# RGB_Panel_v-1.net
KiCad netlist of a schematic drawn in EAGLE
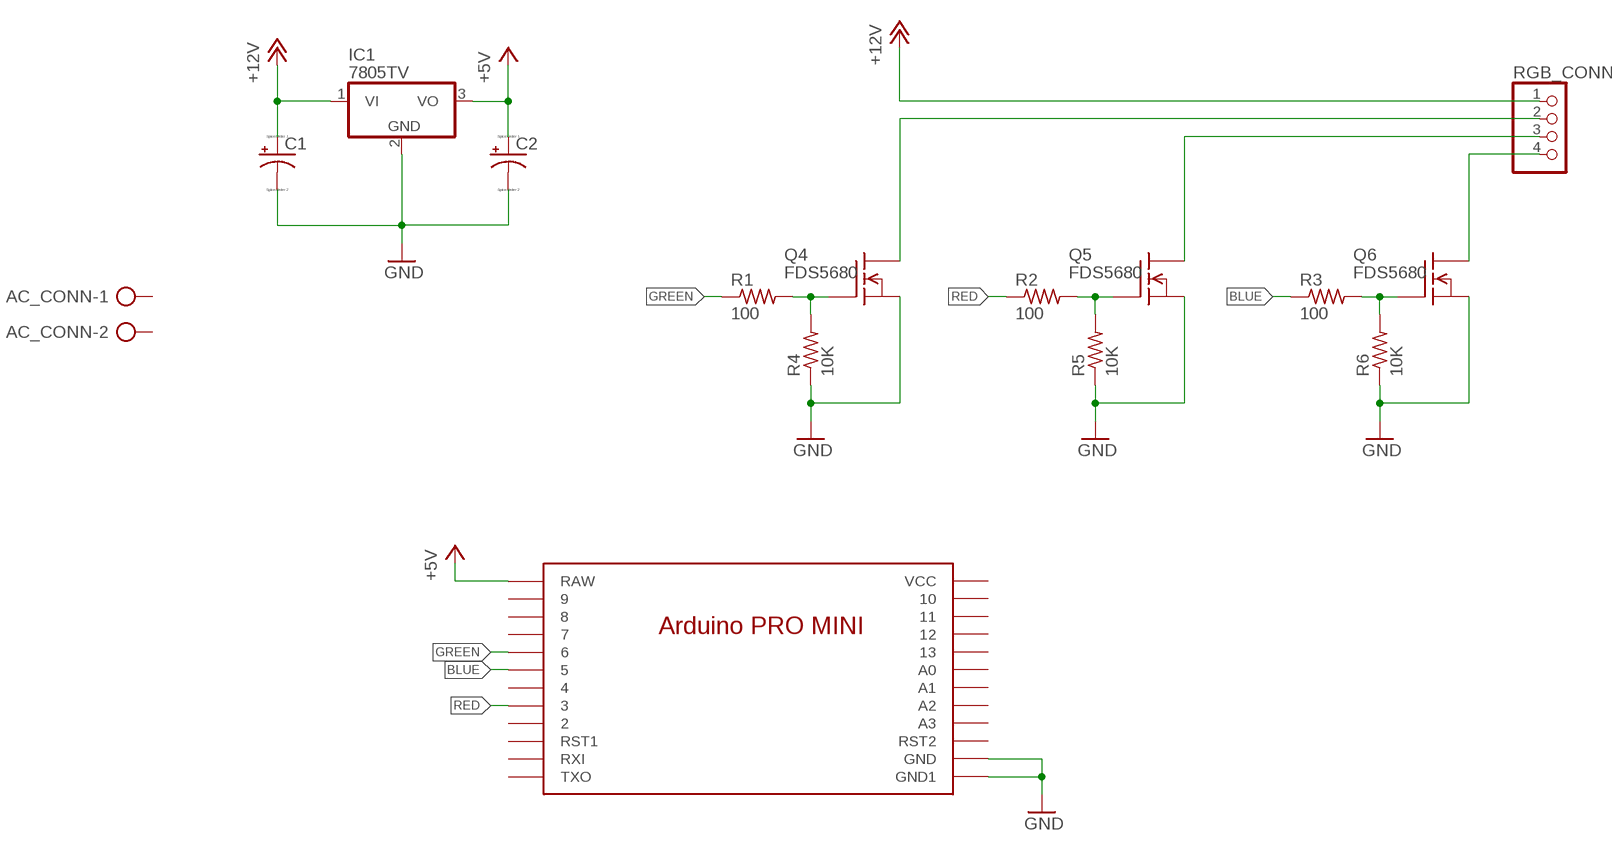
[diagram p0: schematic, sheet 1]

(export (version "E")
  (design (tool "Eeschema 10.0.6"))
  (components
    (comp (ref "AC_CONN")
      (value "AK300/2")
      (footprint "eagle-import:AK300_2")
      (libsource (lib "eagle-import") (part "AK300/2"))
    )
    (comp (ref "C1")
      (value "CPOL-USE2,5-6E")
      (footprint "eagle-import:E2,5-6E")
      (libsource (lib "eagle-import") (part "CPOL-USE2,5-6E"))
    )
    (comp (ref "C2")
      (value "CPOL-USE2,5-6E")
      (footprint "eagle-import:E2,5-6E")
      (libsource (lib "eagle-import") (part "CPOL-USE2,5-6E"))
    )
    (comp (ref "IC1")
      (value "7805TV")
      (footprint "eagle-import:TO220V")
      (libsource (lib "eagle-import") (part "78TV05"))
    )
    (comp (ref "Q4")
      (value "FDS5680")
      (footprint "eagle-import:SO-8")
      (libsource (lib "eagle-import") (part "FDS5680"))
    )
    (comp (ref "Q5")
      (value "FDS5680")
      (footprint "eagle-import:SO-8")
      (libsource (lib "eagle-import") (part "FDS5680"))
    )
    (comp (ref "Q6")
      (value "FDS5680")
      (footprint "eagle-import:SO-8")
      (libsource (lib "eagle-import") (part "FDS5680"))
    )
    (comp (ref "R1")
      (value "100")
      (footprint "eagle-import:0204_7")
      (libsource (lib "eagle-import") (part "R-US_0204/7"))
    )
    (comp (ref "R2")
      (value "100")
      (footprint "eagle-import:0204_7")
      (libsource (lib "eagle-import") (part "R-US_0204/7"))
    )
    (comp (ref "R3")
      (value "100")
      (footprint "eagle-import:0204_7")
      (libsource (lib "eagle-import") (part "R-US_0204/7"))
    )
    (comp (ref "R4")
      (value "10K")
      (footprint "eagle-import:0204_7")
      (libsource (lib "eagle-import") (part "R-US_0204/7"))
    )
    (comp (ref "R5")
      (value "10K")
      (footprint "eagle-import:0204_7")
      (libsource (lib "eagle-import") (part "R-US_0204/7"))
    )
    (comp (ref "R6")
      (value "10K")
      (footprint "eagle-import:0204_7")
      (libsource (lib "eagle-import") (part "R-US_0204/7"))
    )
    (comp (ref "RGB_CONN")
      (value "PINHD-1X4")
      (footprint "eagle-import:1X04")
      (libsource (lib "eagle-import") (part "PINHD-1X4"))
    )
    (comp (ref "U$1")
      (value "NANO")
      (footprint "eagle-import:NANO")
      (libsource (lib "eagle-import") (part "NANO"))
    )
  )
  (nets
    (net (code "1") (name "+5V") (class "Default")
      (node (ref "C2") (pin "+") (pinfunction "+_+") (pintype "passive"))
      (node (ref "IC1") (pin "3") (pinfunction "VO_3") (pintype "passive"))
      (node (ref "U$1") (pin "RAW") (pinfunction "RAW_RAW") (pintype "bidirectional"))
    )
    (net (code "2") (name "+12V") (class "Default")
      (node (ref "C1") (pin "+") (pinfunction "+_+") (pintype "passive"))
      (node (ref "IC1") (pin "1") (pinfunction "VI_1") (pintype "input"))
      (node (ref "RGB_CONN") (pin "1") (pinfunction "1_1") (pintype "passive"))
    )
    (net (code "3") (name "BLUE") (class "Default")
      (node (ref "R3") (pin "1") (pinfunction "1_1") (pintype "passive"))
      (node (ref "U$1") (pin "5") (pinfunction "5_5") (pintype "bidirectional"))
    )
    (net (code "4") (name "GND") (class "Default")
      (node (ref "C1") (pin "-") (pinfunction "-_-") (pintype "passive"))
      (node (ref "C2") (pin "-") (pinfunction "-_-") (pintype "passive"))
      (node (ref "IC1") (pin "2") (pinfunction "GND_2") (pintype "passive"))
      (node (ref "Q4") (pin "1") (pinfunction "S_1") (pintype "passive"))
      (node (ref "Q4") (pin "2") (pinfunction "S_2") (pintype "passive"))
      (node (ref "Q4") (pin "3") (pinfunction "S_3") (pintype "passive"))
      (node (ref "Q5") (pin "1") (pinfunction "S_1") (pintype "passive"))
      (node (ref "Q5") (pin "2") (pinfunction "S_2") (pintype "passive"))
      (node (ref "Q5") (pin "3") (pinfunction "S_3") (pintype "passive"))
      (node (ref "Q6") (pin "1") (pinfunction "S_1") (pintype "passive"))
      (node (ref "Q6") (pin "2") (pinfunction "S_2") (pintype "passive"))
      (node (ref "Q6") (pin "3") (pinfunction "S_3") (pintype "passive"))
      (node (ref "R4") (pin "1") (pinfunction "1_1") (pintype "passive"))
      (node (ref "R5") (pin "1") (pinfunction "1_1") (pintype "passive"))
      (node (ref "R6") (pin "1") (pinfunction "1_1") (pintype "passive"))
      (node (ref "U$1") (pin "GND1") (pinfunction "GND_GND1") (pintype "bidirectional"))
      (node (ref "U$1") (pin "GND2") (pinfunction "GND1_GND2") (pintype "power_in"))
    )
    (net (code "5") (name "GREEN") (class "Default")
      (node (ref "R1") (pin "1") (pinfunction "1_1") (pintype "passive"))
      (node (ref "U$1") (pin "6") (pinfunction "6_6") (pintype "bidirectional"))
    )
    (net (code "6") (name "Net-(Q4-D-Pad5)") (class "Default")
      (node (ref "Q4") (pin "5") (pinfunction "D_5") (pintype "passive"))
      (node (ref "Q4") (pin "6") (pinfunction "D_6") (pintype "passive"))
      (node (ref "Q4") (pin "7") (pinfunction "D_7") (pintype "passive"))
      (node (ref "Q4") (pin "8") (pinfunction "D_8") (pintype "passive"))
      (node (ref "RGB_CONN") (pin "2") (pinfunction "2_2") (pintype "passive"))
    )
    (net (code "7") (name "Net-(Q4-G)") (class "Default")
      (node (ref "Q4") (pin "4") (pinfunction "G_4") (pintype "passive"))
      (node (ref "R1") (pin "2") (pinfunction "2_2") (pintype "passive"))
      (node (ref "R4") (pin "2") (pinfunction "2_2") (pintype "passive"))
    )
    (net (code "8") (name "Net-(Q5-D-Pad5)") (class "Default")
      (node (ref "Q5") (pin "5") (pinfunction "D_5") (pintype "passive"))
      (node (ref "Q5") (pin "6") (pinfunction "D_6") (pintype "passive"))
      (node (ref "Q5") (pin "7") (pinfunction "D_7") (pintype "passive"))
      (node (ref "Q5") (pin "8") (pinfunction "D_8") (pintype "passive"))
      (node (ref "RGB_CONN") (pin "3") (pinfunction "3_3") (pintype "passive"))
    )
    (net (code "9") (name "Net-(Q5-G)") (class "Default")
      (node (ref "Q5") (pin "4") (pinfunction "G_4") (pintype "passive"))
      (node (ref "R2") (pin "2") (pinfunction "2_2") (pintype "passive"))
      (node (ref "R5") (pin "2") (pinfunction "2_2") (pintype "passive"))
    )
    (net (code "10") (name "Net-(Q6-D-Pad5)") (class "Default")
      (node (ref "Q6") (pin "5") (pinfunction "D_5") (pintype "passive"))
      (node (ref "Q6") (pin "6") (pinfunction "D_6") (pintype "passive"))
      (node (ref "Q6") (pin "7") (pinfunction "D_7") (pintype "passive"))
      (node (ref "Q6") (pin "8") (pinfunction "D_8") (pintype "passive"))
      (node (ref "RGB_CONN") (pin "4") (pinfunction "4_4") (pintype "passive"))
    )
    (net (code "11") (name "Net-(Q6-G)") (class "Default")
      (node (ref "Q6") (pin "4") (pinfunction "G_4") (pintype "passive"))
      (node (ref "R3") (pin "2") (pinfunction "2_2") (pintype "passive"))
      (node (ref "R6") (pin "2") (pinfunction "2_2") (pintype "passive"))
    )
    (net (code "12") (name "RED") (class "Default")
      (node (ref "R2") (pin "1") (pinfunction "1_1") (pintype "passive"))
      (node (ref "U$1") (pin "3") (pinfunction "3_3") (pintype "bidirectional"))
    )
    (net (code "13") (name "unconnected-(AC_CONNA-KL-Pad1)") (class "Default")
      (node (ref "AC_CONN") (pin "1") (pinfunction "KL_1") (pintype "passive"))
    )
    (net (code "14") (name "unconnected-(AC_CONNB-KL-Pad2)") (class "Default")
      (node (ref "AC_CONN") (pin "2") (pinfunction "KL_2") (pintype "passive"))
    )
    (net (code "15") (name "unconnected-(U$1-Pad2)") (class "Default")
      (node (ref "U$1") (pin "2") (pinfunction "2_2") (pintype "bidirectional"))
    )
    (net (code "16") (name "unconnected-(U$1-Pad4)") (class "Default")
      (node (ref "U$1") (pin "4") (pinfunction "4_4") (pintype "bidirectional"))
    )
    (net (code "17") (name "unconnected-(U$1-Pad7)") (class "Default")
      (node (ref "U$1") (pin "7") (pinfunction "7_7") (pintype "bidirectional"))
    )
    (net (code "18") (name "unconnected-(U$1-Pad8)") (class "Default")
      (node (ref "U$1") (pin "8") (pinfunction "8_8") (pintype "bidirectional"))
    )
    (net (code "19") (name "unconnected-(U$1-Pad9)") (class "Default")
      (node (ref "U$1") (pin "9") (pinfunction "9_9") (pintype "bidirectional"))
    )
    (net (code "20") (name "unconnected-(U$1-Pad10)") (class "Default")
      (node (ref "U$1") (pin "10") (pinfunction "10_10") (pintype "bidirectional"))
    )
    (net (code "21") (name "unconnected-(U$1-Pad11)") (class "Default")
      (node (ref "U$1") (pin "11") (pinfunction "11_11") (pintype "bidirectional"))
    )
    (net (code "22") (name "unconnected-(U$1-Pad12)") (class "Default")
      (node (ref "U$1") (pin "12") (pinfunction "12_12") (pintype "bidirectional"))
    )
    (net (code "23") (name "unconnected-(U$1-Pad13)") (class "Default")
      (node (ref "U$1") (pin "13") (pinfunction "13_13") (pintype "bidirectional"))
    )
    (net (code "24") (name "unconnected-(U$1-PadA0)") (class "Default")
      (node (ref "U$1") (pin "A0") (pinfunction "A0_A0") (pintype "bidirectional"))
    )
    (net (code "25") (name "unconnected-(U$1-PadA1)") (class "Default")
      (node (ref "U$1") (pin "A1") (pinfunction "A1_A1") (pintype "bidirectional"))
    )
    (net (code "26") (name "unconnected-(U$1-PadA2)") (class "Default")
      (node (ref "U$1") (pin "A2") (pinfunction "A2_A2") (pintype "bidirectional"))
    )
    (net (code "27") (name "unconnected-(U$1-PadA3)") (class "Default")
      (node (ref "U$1") (pin "A3") (pinfunction "A3_A3") (pintype "bidirectional"))
    )
    (net (code "28") (name "unconnected-(U$1-PadRST1)") (class "Default")
      (node (ref "U$1") (pin "RST1") (pinfunction "RST1_RST1") (pintype "bidirectional"))
    )
    (net (code "29") (name "unconnected-(U$1-PadRST2)") (class "Default")
      (node (ref "U$1") (pin "RST2") (pinfunction "RST2_RST2") (pintype "bidirectional"))
    )
    (net (code "30") (name "unconnected-(U$1-PadRXI)") (class "Default")
      (node (ref "U$1") (pin "RXI") (pinfunction "RXI_RXI") (pintype "bidirectional"))
    )
    (net (code "31") (name "unconnected-(U$1-PadTXO)") (class "Default")
      (node (ref "U$1") (pin "TXO") (pinfunction "TXO_TXO") (pintype "bidirectional"))
    )
    (net (code "32") (name "unconnected-(U$1-PadVCC)") (class "Default")
      (node (ref "U$1") (pin "VCC") (pinfunction "VCC_VCC") (pintype "bidirectional"))
    )
  )
)
